# DAC.net
KiCad netlist of a schematic drawn in Altium Designer
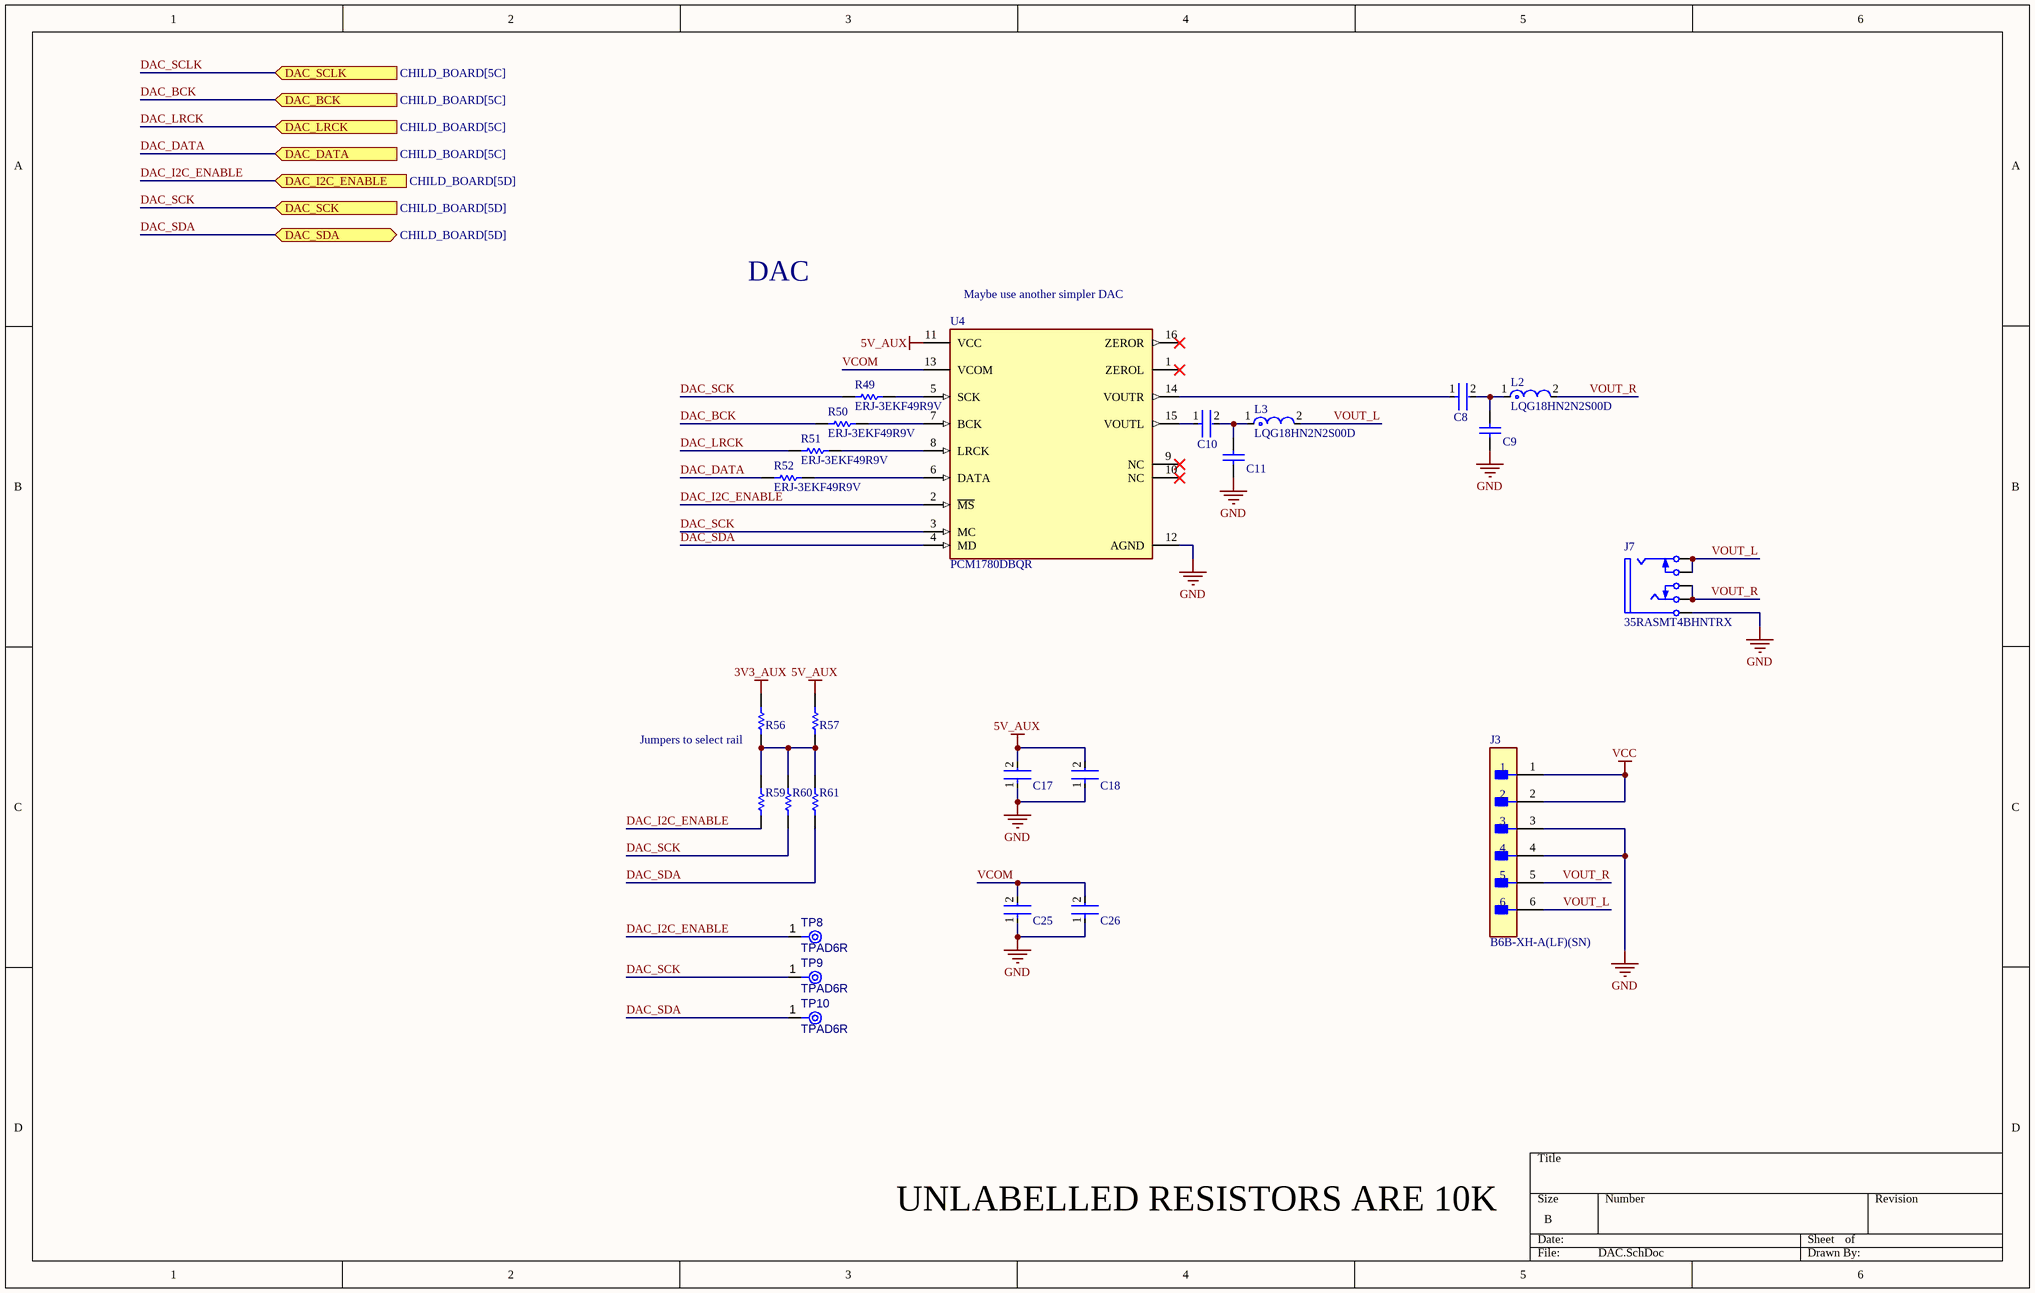
[diagram p0: DAC.SchDoc]

(export (version "E")
  (design (tool "Eeschema 10.0.6"))
  (components
    (comp (ref "C8")
      (value "GRM188R60J106ME47D")
      (footprint "FP-GRM188-0_1-e0_2_0_55-IPC_A")
      (description "Chip Multilayer Ceramic Capacitors for General Purpose, 0603, 10uF, X5R, 15%, 20%, 6.3V")
      (fields (field (name "VOLTAGE") "6.3V") (field (name "TOLERANCE") "20%"))
      (libsource (lib "Altium Content Vault") (part "02cd4be3c70576c341d710602a673aa"))
    )
    (comp (ref "C9")
      (value "0603 CAP")
      (footprint "CAPC1608X90X40ML10T20")
      (description "0pF 0603 capacitor placeholder")
      (libsource (lib "uORocketry Hardware") (part "CAP-NP-2"))
    )
    (comp (ref "C10")
      (value "GRM188R60J106ME47D")
      (footprint "FP-GRM188-0_1-e0_2_0_55-IPC_A")
      (description "Chip Multilayer Ceramic Capacitors for General Purpose, 0603, 10uF, X5R, 15%, 20%, 6.3V")
      (fields (field (name "VOLTAGE") "6.3V") (field (name "TOLERANCE") "20%"))
      (libsource (lib "Altium Content Vault") (part "02cd4be3c70576c341d710602a673aa"))
    )
    (comp (ref "C11")
      (value "0603 CAP")
      (footprint "CAPC1608X90X40ML10T20")
      (description "0pF 0603 capacitor placeholder")
      (libsource (lib "uORocketry Hardware") (part "CAP-NP-2"))
    )
    (comp (ref "C17")
      (value "GRM188R60J106ME47D")
      (footprint "FP-GRM188-0_1-e0_2_0_55-IPC_A")
      (description "Chip Multilayer Ceramic Capacitors for General Purpose, 0603, 10uF, X5R, 15%, 20%, 6.3V")
      (fields (field (name "VOLTAGE") "6.3V") (field (name "TOLERANCE") "20%"))
      (libsource (lib "Altium Content Vault") (part "02cd4be3c70576c341d710602a673aa"))
    )
    (comp (ref "C18")
      (value "C1005X7R1H104K050BB")
      (footprint "FP-C1005-050-0_05-IPC_C")
      (description "Multilayer Ceramic Capacitors 100nF ±10% 50V X7R SMD 0402")
      (fields (field (name "VOLTAGE") "50V") (field (name "TOLERANCE") "10%"))
      (libsource (lib "Altium Content Vault") (part "b4654b650e69147ec39a6b967a45e02"))
    )
    (comp (ref "C25")
      (value "GRM188R60J106ME47D")
      (footprint "FP-GRM188-0_1-e0_2_0_55-IPC_A")
      (description "Chip Multilayer Ceramic Capacitors for General Purpose, 0603, 10uF, X5R, 15%, 20%, 6.3V")
      (fields (field (name "VOLTAGE") "6.3V") (field (name "TOLERANCE") "20%"))
      (libsource (lib "Altium Content Vault") (part "02cd4be3c70576c341d710602a673aa"))
    )
    (comp (ref "C26")
      (value "C1005X7R1H104K050BB")
      (footprint "FP-C1005-050-0_05-IPC_C")
      (description "Multilayer Ceramic Capacitors 100nF ±10% 50V X7R SMD 0402")
      (fields (field (name "VOLTAGE") "50V") (field (name "TOLERANCE") "10%"))
      (libsource (lib "Altium Content Vault") (part "b4654b650e69147ec39a6b967a45e02"))
    )
    (comp (ref "J3")
      (value "B6B-XH-A(LF)(SN)")
      (footprint "FP-B6B-XH-A_LF_SN-MFG")
      (description "CONN HEADER VERT 6POS 2.5MM")
      (libsource (lib "Altium Content Vault") (part "f2cb566baf1c37ab5a3b8e90bbeafd6"))
    )
    (comp (ref "J7")
      (value "35RASMT4BHNTRX")
      (footprint "SWIT-35RASMT4BHNTRX_V")
      (description "Female 3.5 mm Phone Jack, 5 Position, Height 5 mm, RoHS, Tape and Reel")
      (libsource (lib "Altium Content Vault") (part "JACK-3CD5-RN"))
    )
    (comp (ref "L2")
      (value "LQG18HN2N2S00D")
      (footprint "FP-LQG18HH_00-IPC_A")
      (description "Multilayer type RF Inductor 2.2nH ±0.3nH 0.1Ω 1100mA 0603")
      (libsource (lib "Altium Content Vault") (part "4cc4b267dca4c8e51f7102f422741d8"))
    )
    (comp (ref "L3")
      (value "LQG18HN2N2S00D")
      (footprint "FP-LQG18HH_00-IPC_A")
      (description "Multilayer type RF Inductor 2.2nH ±0.3nH 0.1Ω 1100mA 0603")
      (libsource (lib "Altium Content Vault") (part "4cc4b267dca4c8e51f7102f422741d8"))
    )
    (comp (ref "R49")
      (value "ERJ-3EKF49R9V")
      (footprint "RESC1608X55X30ML15T15")
      (fields (field (name "MANUFACTURER") "Panasonic"))
      (libsource (lib "Altium Content Vault") (part "RES"))
    )
    (comp (ref "R50")
      (value "ERJ-3EKF49R9V")
      (footprint "RESC1608X55X30ML15T15")
      (fields (field (name "MANUFACTURER") "Panasonic"))
      (libsource (lib "Altium Content Vault") (part "RES"))
    )
    (comp (ref "R51")
      (value "ERJ-3EKF49R9V")
      (footprint "RESC1608X55X30ML15T15")
      (fields (field (name "MANUFACTURER") "Panasonic"))
      (libsource (lib "Altium Content Vault") (part "RES"))
    )
    (comp (ref "R52")
      (value "ERJ-3EKF49R9V")
      (footprint "RESC1608X55X30ML15T15")
      (fields (field (name "MANUFACTURER") "Panasonic"))
      (libsource (lib "Altium Content Vault") (part "RES"))
    )
    (comp (ref "R56")
      (value "0402 JUMPER 0 OHM")
      (footprint "RESC1005X40X25NL05T05")
      (description "READ THE NAME")
      (libsource (lib "uORocketry Hardware") (part "RES"))
    )
    (comp (ref "R57")
      (value "0402 JUMPER 0 OHM")
      (footprint "RESC1005X40X25NL05T05")
      (description "READ THE NAME")
      (libsource (lib "uORocketry Hardware") (part "RES"))
    )
    (comp (ref "R59")
      (value "ERJ3EKF1002V")
      (footprint "RESC1609X55X30LL15T15")
      (description "Chip Resistor, 10 KOhm, +/- 1%, 0.1 W, -55 to 155 degC, 0603 (1608 Metric), RoHS, Tape and Reel")
      (fields (field (name "TOLERANCE") "1%") (field (name "MANUFACTURER") "Panasonic"))
      (libsource (lib "Altium Content Vault") (part "RES-2"))
    )
    (comp (ref "R60")
      (value "ERJ3EKF1002V")
      (footprint "RESC1609X55X30LL15T15")
      (description "Chip Resistor, 10 KOhm, +/- 1%, 0.1 W, -55 to 155 degC, 0603 (1608 Metric), RoHS, Tape and Reel")
      (fields (field (name "TOLERANCE") "1%") (field (name "MANUFACTURER") "Panasonic"))
      (libsource (lib "Altium Content Vault") (part "RES-2"))
    )
    (comp (ref "R61")
      (value "ERJ3EKF1002V")
      (footprint "RESC1609X55X30LL15T15")
      (description "Chip Resistor, 10 KOhm, +/- 1%, 0.1 W, -55 to 155 degC, 0603 (1608 Metric), RoHS, Tape and Reel")
      (fields (field (name "TOLERANCE") "1%") (field (name "MANUFACTURER") "Panasonic"))
      (libsource (lib "Altium Content Vault") (part "RES-2"))
    )
    (comp (ref "TP8")
      (value "TPAD6R")
      (footprint "TP06R")
      (description "0.6mm round")
      (libsource (lib "uORocketry Hardware") (part "CMP-001-0001-4"))
    )
    (comp (ref "TP9")
      (value "TPAD6R")
      (footprint "TP06R")
      (description "0.6mm round")
      (libsource (lib "uORocketry Hardware") (part "CMP-001-0001-4"))
    )
    (comp (ref "TP10")
      (value "TPAD6R")
      (footprint "TP06R")
      (description "0.6mm round")
      (libsource (lib "uORocketry Hardware") (part "CMP-001-0001-4"))
    )
    (comp (ref "U4")
      (value "PCM1780DBQR")
      (footprint "FP-DBQ0016A-IPC_C")
      (description "IC DAC/AUDIO 24BIT 200K 16SSOP")
      (libsource (lib "Altium Content Vault") (part "df9593e9496f7d97fc821e4a000630f"))
    )
  )
  (nets
    (net (code "1") (name "/DAC_BCK") (class "Default")
      (node (ref "R50") (pin "2") (pinfunction "2_2") (pintype "passive"))
    )
    (net (code "2") (name "/DAC_DATA") (class "Default")
      (node (ref "R52") (pin "2") (pinfunction "2_2") (pintype "passive"))
    )
    (net (code "3") (name "/DAC_I2C_ENABLE") (class "Default")
      (node (ref "R59") (pin "1") (pinfunction "1_1") (pintype "passive"))
      (node (ref "TP8") (pin "1") (pinfunction "TP_1") (pintype "passive"))
      (node (ref "U4") (pin "2") (pinfunction "~{MS}_2") (pintype "input"))
    )
    (net (code "4") (name "/DAC_LRCK") (class "Default")
      (node (ref "R51") (pin "2") (pinfunction "2_2") (pintype "passive"))
    )
    (net (code "5") (name "/DAC_SCK") (class "Default")
      (node (ref "R49") (pin "2") (pinfunction "2_2") (pintype "passive"))
      (node (ref "R60") (pin "1") (pinfunction "1_1") (pintype "passive"))
      (node (ref "TP9") (pin "1") (pinfunction "TP_1") (pintype "passive"))
      (node (ref "U4") (pin "3") (pinfunction "MC_3") (pintype "input"))
    )
    (net (code "7") (name "/DAC_SDA") (class "Default")
      (node (ref "R61") (pin "1") (pinfunction "1_1") (pintype "passive"))
      (node (ref "TP10") (pin "1") (pinfunction "TP_1") (pintype "passive"))
      (node (ref "U4") (pin "4") (pinfunction "MD_4") (pintype "input"))
    )
    (net (code "8") (name "/VCOM") (class "Default")
      (node (ref "C25") (pin "2") (pinfunction "2_2") (pintype "passive"))
      (node (ref "C26") (pin "2") (pinfunction "2_2") (pintype "passive"))
      (node (ref "U4") (pin "13") (pinfunction "VCOM_13") (pintype "power_in"))
    )
    (net (code "9") (name "/VOUT_L") (class "Default")
      (node (ref "J3") (pin "6") (pinfunction "6_6") (pintype "passive"))
      (node (ref "J7") (pin "2") (pinfunction "2_2") (pintype "passive"))
      (node (ref "J7") (pin "4") (pinfunction "4_4") (pintype "passive"))
      (node (ref "L3") (pin "2") (pinfunction "2_2") (pintype "passive"))
    )
    (net (code "10") (name "/VOUT_R") (class "Default")
      (node (ref "J3") (pin "5") (pinfunction "5_5") (pintype "passive"))
      (node (ref "J7") (pin "3") (pinfunction "3_3") (pintype "passive"))
      (node (ref "J7") (pin "5") (pinfunction "5_5") (pintype "passive"))
      (node (ref "L2") (pin "2") (pinfunction "2_2") (pintype "passive"))
    )
    (net (code "11") (name "3V3_AUX") (class "Default")
      (node (ref "R56") (pin "2") (pinfunction "2_2") (pintype "passive"))
    )
    (net (code "12") (name "5V_AUX") (class "Default")
      (node (ref "C17") (pin "2") (pinfunction "2_2") (pintype "passive"))
      (node (ref "C18") (pin "2") (pinfunction "2_2") (pintype "passive"))
      (node (ref "R57") (pin "2") (pinfunction "2_2") (pintype "passive"))
      (node (ref "U4") (pin "11") (pinfunction "VCC_11") (pintype "power_in"))
    )
    (net (code "13") (name "GND") (class "Default")
      (node (ref "C11") (pin "1") (pinfunction "1_1") (pintype "passive"))
      (node (ref "C17") (pin "1") (pinfunction "1_1") (pintype "passive"))
      (node (ref "C18") (pin "1") (pinfunction "1_1") (pintype "passive"))
      (node (ref "C25") (pin "1") (pinfunction "1_1") (pintype "passive"))
      (node (ref "C26") (pin "1") (pinfunction "1_1") (pintype "passive"))
      (node (ref "C9") (pin "1") (pinfunction "1_1") (pintype "passive"))
      (node (ref "J3") (pin "3") (pinfunction "3_3") (pintype "passive"))
      (node (ref "J3") (pin "4") (pinfunction "4_4") (pintype "passive"))
      (node (ref "J7") (pin "1") (pinfunction "1_1") (pintype "passive"))
      (node (ref "U4") (pin "12") (pinfunction "AGND_12") (pintype "power_in"))
    )
    (net (code "14") (name "Net-(C8-Pad2)") (class "Default")
      (node (ref "C8") (pin "2") (pinfunction "2_2") (pintype "passive"))
      (node (ref "C9") (pin "2") (pinfunction "2_2") (pintype "passive"))
      (node (ref "L2") (pin "1") (pinfunction "1_1") (pintype "passive"))
    )
    (net (code "15") (name "Net-(C10-Pad2)") (class "Default")
      (node (ref "C10") (pin "2") (pinfunction "2_2") (pintype "passive"))
      (node (ref "C11") (pin "2") (pinfunction "2_2") (pintype "passive"))
      (node (ref "L3") (pin "1") (pinfunction "1_1") (pintype "passive"))
    )
    (net (code "16") (name "Net-(R56-Pad1)") (class "Default")
      (node (ref "R56") (pin "1") (pinfunction "1_1") (pintype "passive"))
      (node (ref "R57") (pin "1") (pinfunction "1_1") (pintype "passive"))
      (node (ref "R59") (pin "2") (pinfunction "2_2") (pintype "passive"))
      (node (ref "R60") (pin "2") (pinfunction "2_2") (pintype "passive"))
      (node (ref "R61") (pin "2") (pinfunction "2_2") (pintype "passive"))
    )
    (net (code "17") (name "Net-(U4-BCK)") (class "Default")
      (node (ref "R50") (pin "1") (pinfunction "1_1") (pintype "passive"))
      (node (ref "U4") (pin "7") (pinfunction "BCK_7") (pintype "input"))
    )
    (net (code "18") (name "Net-(U4-DATA)") (class "Default")
      (node (ref "R52") (pin "1") (pinfunction "1_1") (pintype "passive"))
      (node (ref "U4") (pin "6") (pinfunction "DATA_6") (pintype "input"))
    )
    (net (code "19") (name "Net-(U4-LRCK)") (class "Default")
      (node (ref "R51") (pin "1") (pinfunction "1_1") (pintype "passive"))
      (node (ref "U4") (pin "8") (pinfunction "LRCK_8") (pintype "input"))
    )
    (net (code "20") (name "Net-(U4-SCK)") (class "Default")
      (node (ref "R49") (pin "1") (pinfunction "1_1") (pintype "passive"))
      (node (ref "U4") (pin "5") (pinfunction "SCK_5") (pintype "input"))
    )
    (net (code "21") (name "Net-(U4-VOUTL)") (class "Default")
      (node (ref "C10") (pin "1") (pinfunction "1_1") (pintype "passive"))
      (node (ref "U4") (pin "15") (pinfunction "VOUTL_15") (pintype "output"))
    )
    (net (code "22") (name "Net-(U4-VOUTR)") (class "Default")
      (node (ref "C8") (pin "1") (pinfunction "1_1") (pintype "passive"))
      (node (ref "U4") (pin "14") (pinfunction "VOUTR_14") (pintype "output"))
    )
    (net (code "23") (name "VCC") (class "Default")
      (node (ref "J3") (pin "1") (pinfunction "1_1") (pintype "passive"))
      (node (ref "J3") (pin "2") (pinfunction "2_2") (pintype "passive"))
    )
    (net (code "24") (name "unconnected-(U4-NC-Pad9)") (class "Default")
      (node (ref "U4") (pin "9") (pinfunction "NC_9") (pintype "passive+no_connect"))
    )
    (net (code "25") (name "unconnected-(U4-NC-Pad10)") (class "Default")
      (node (ref "U4") (pin "10") (pinfunction "NC_10") (pintype "passive+no_connect"))
    )
    (net (code "26") (name "unconnected-(U4-ZEROL-Pad1)") (class "Default")
      (node (ref "U4") (pin "1") (pinfunction "ZEROL_1") (pintype "passive+no_connect"))
    )
    (net (code "27") (name "unconnected-(U4-ZEROR-Pad16)") (class "Default")
      (node (ref "U4") (pin "16") (pinfunction "ZEROR_16") (pintype "output+no_connect"))
    )
  )
)
